# SCH_USB-Hub_2024-07-14.net
KiCad netlist of a schematic drawn in EasyEDA
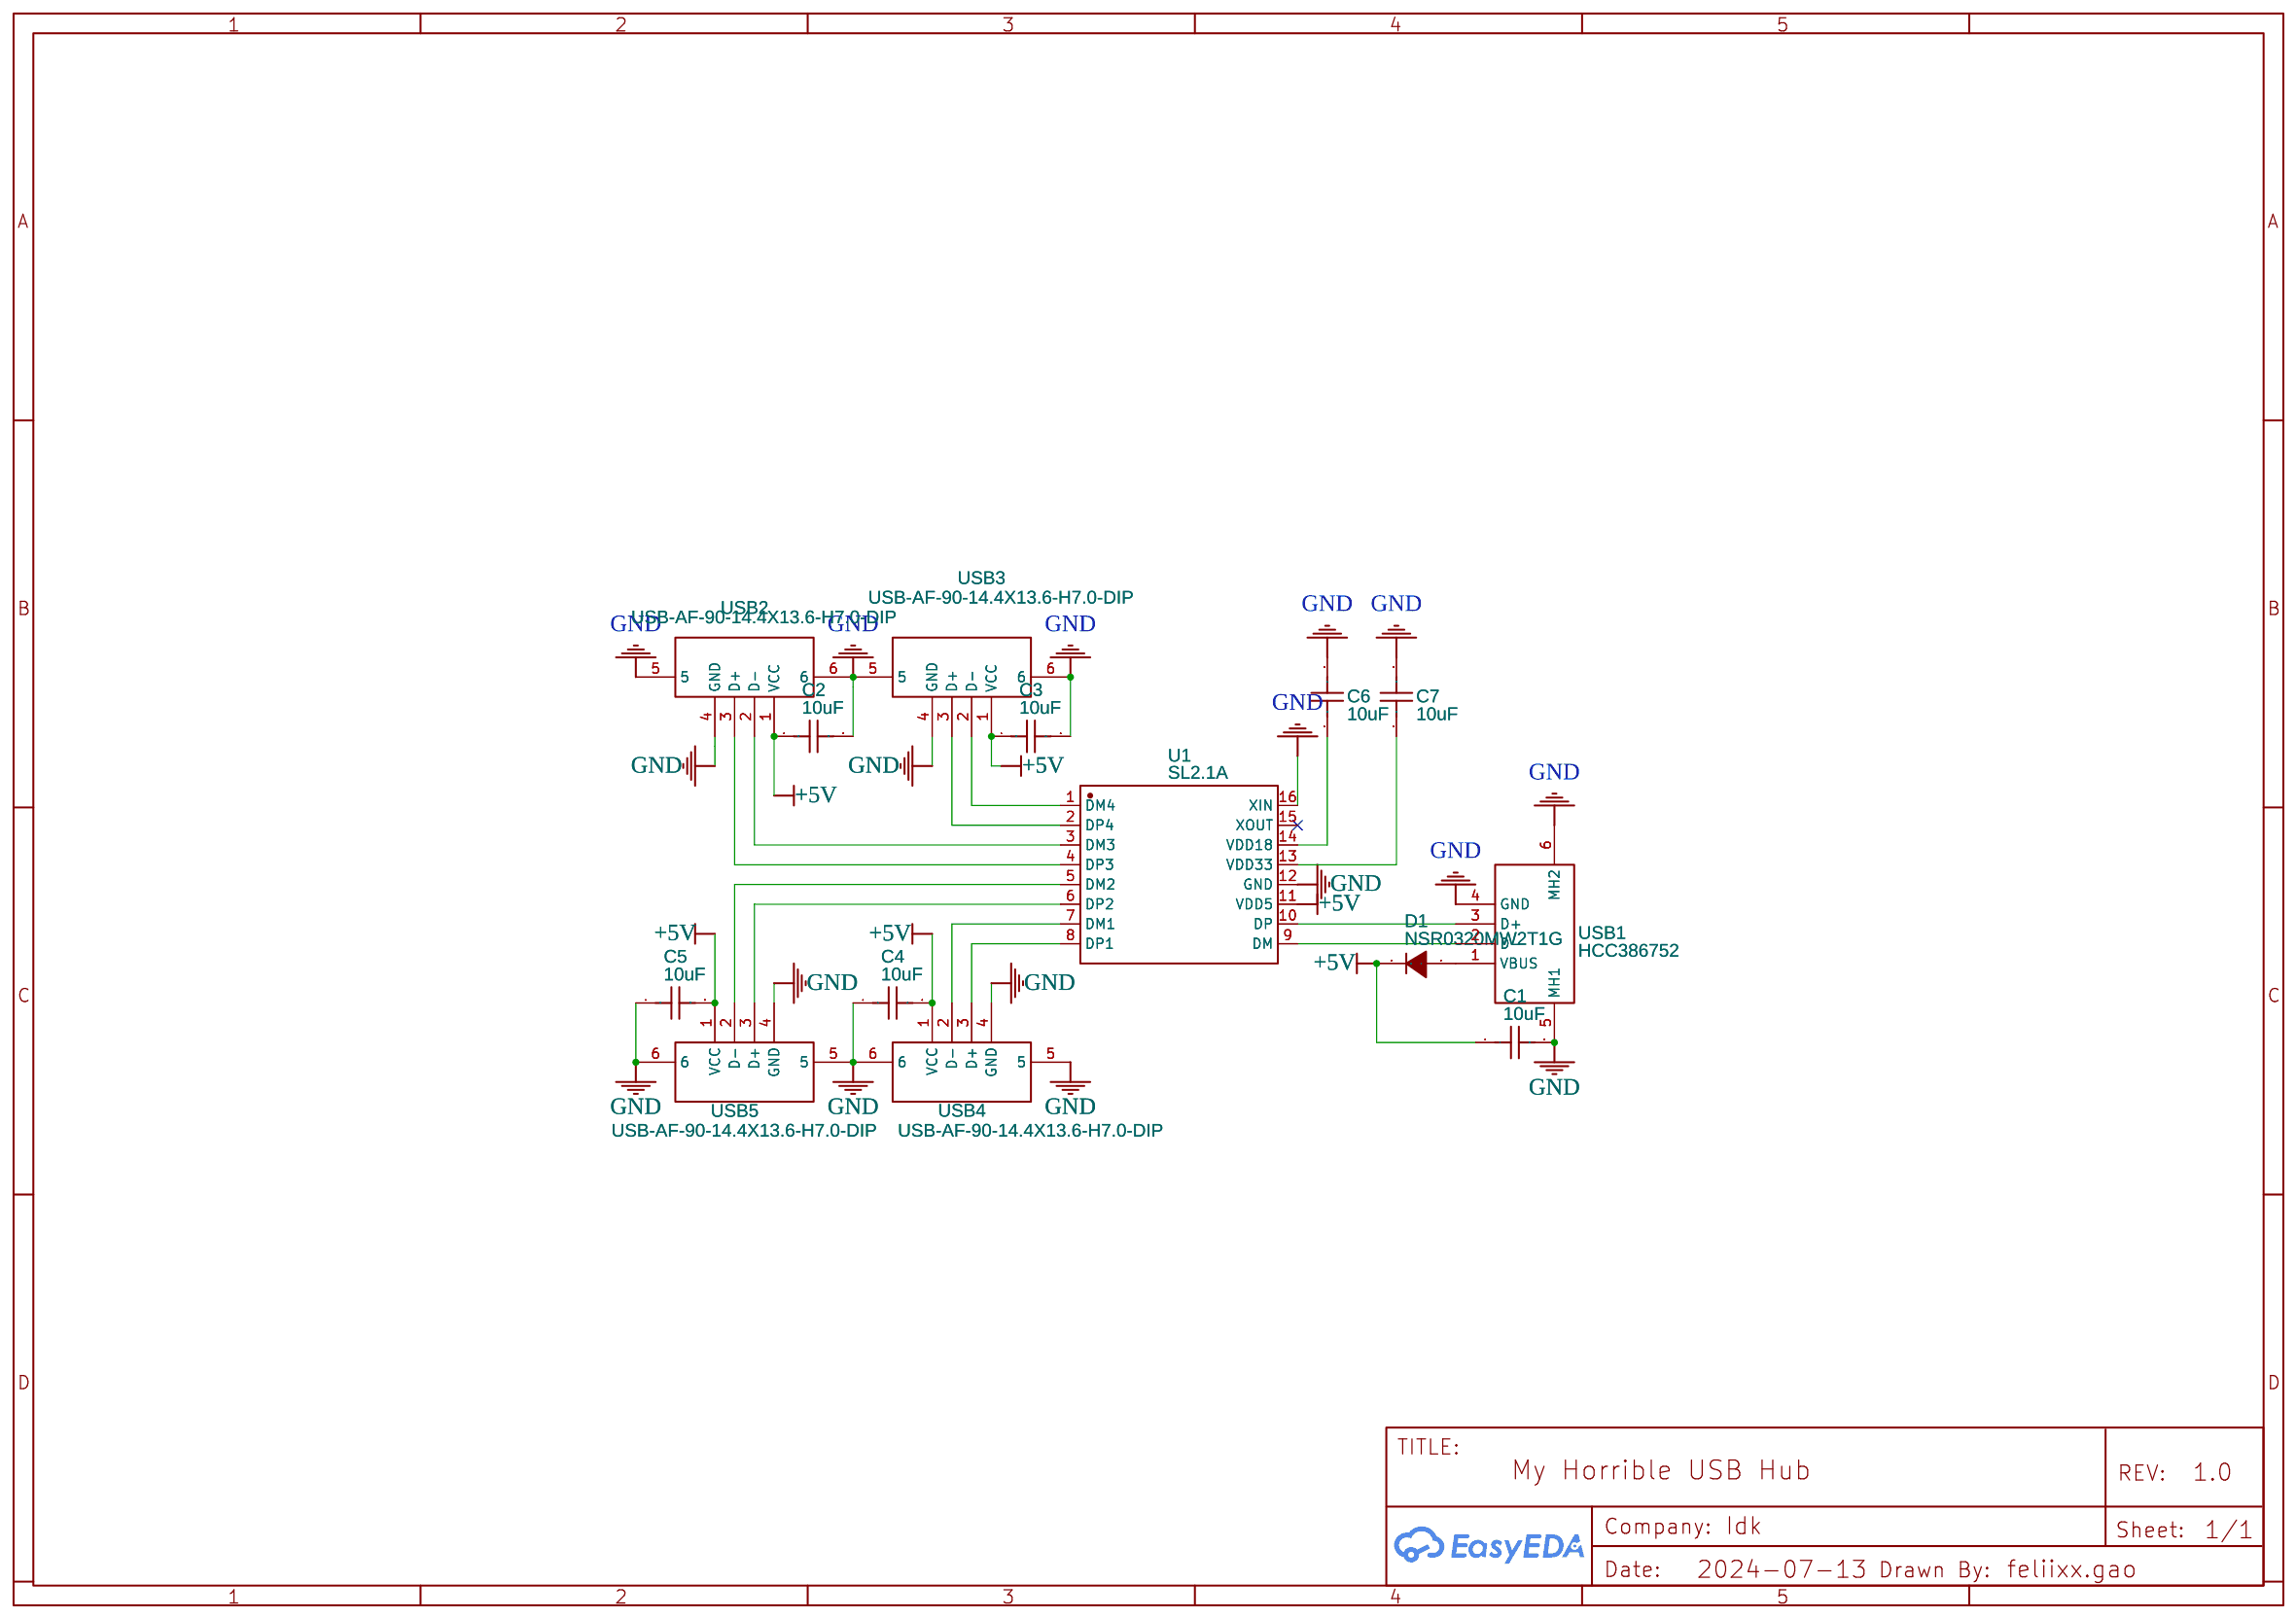
[diagram p0: schematic sheet]

(export (version "E")
  (design (tool "Eeschema 10.0.6"))
  (components
    (comp (ref "C1")
      (value "10uF")
      (fields
        (field (name "Manufacturer Part") "CL10A106KP8NNNC")
        (field (name "Manufacturer") "SAMSUNG(三星)")
      )
      (libsource (lib "") (part "CL10A106KP8NNNC"))
    )
    (comp (ref "C2")
      (value "10uF")
      (fields
        (field (name "Manufacturer Part") "CL10A106KP8NNNC")
        (field (name "Manufacturer") "SAMSUNG(三星)")
      )
      (libsource (lib "") (part "CL10A106KP8NNNC"))
    )
    (comp (ref "C3")
      (value "10uF")
      (fields
        (field (name "Manufacturer Part") "CL10A106KP8NNNC")
        (field (name "Manufacturer") "SAMSUNG(三星)")
      )
      (libsource (lib "") (part "CL10A106KP8NNNC"))
    )
    (comp (ref "C4")
      (value "10uF")
      (fields
        (field (name "Manufacturer Part") "CL10A106KP8NNNC")
        (field (name "Manufacturer") "SAMSUNG(三星)")
      )
      (libsource (lib "") (part "CL10A106KP8NNNC"))
    )
    (comp (ref "C5")
      (value "10uF")
      (fields
        (field (name "Manufacturer Part") "CL10A106KP8NNNC")
        (field (name "Manufacturer") "SAMSUNG(三星)")
      )
      (libsource (lib "") (part "CL10A106KP8NNNC"))
    )
    (comp (ref "C6")
      (value "10uF")
      (fields
        (field (name "Manufacturer Part") "CL10A106KP8NNNC")
        (field (name "Manufacturer") "SAMSUNG(三星)")
      )
      (libsource (lib "") (part "CL10A106KP8NNNC_1"))
    )
    (comp (ref "C7")
      (value "10uF")
      (fields
        (field (name "Manufacturer Part") "CL10A106KP8NNNC")
        (field (name "Manufacturer") "SAMSUNG(三星)")
      )
      (libsource (lib "") (part "CL10A106KP8NNNC_1"))
    )
    (comp (ref "D1")
      (value "NSR0320MW2T1G")
      (fields (field (name "Manufacturer") "onsemi(安森美)"))
      (libsource (lib "") (part "NSR0320MW2T1G"))
    )
    (comp (ref "U1")
      (value "SL2.1A")
      (fields (field (name "Manufacturer") "CoreChips(和芯润德)"))
      (libsource (lib "") (part "SL2.1A"))
    )
    (comp (ref "USB1")
      (value "HCC386752")
      (fields (field (name "Manufacturer Part") "U-USBAR04P-M003") (field (name "Manufacturer") "Ckmtw(灿科盟)"))
      (libsource (lib "") (part "HCC386752"))
    )
    (comp (ref "USB2")
      (value "USB-AF-90-14.4X13.6-H7.0-DIP")
      (fields (field (name "Manufacturer Part") "903-131A1011D10100") (field (name "Manufacturer") "精拓金"))
      (libsource (lib "") (part "USB-AF-90-14.4X13.6-H7.0-DIP"))
    )
    (comp (ref "USB3")
      (value "USB-AF-90-14.4X13.6-H7.0-DIP")
      (fields (field (name "Manufacturer Part") "903-131A1011D10100") (field (name "Manufacturer") "精拓金"))
      (libsource (lib "") (part "USB-AF-90-14.4X13.6-H7.0-DIP"))
    )
    (comp (ref "USB4")
      (value "USB-AF-90-14.4X13.6-H7.0-DIP")
      (fields (field (name "Manufacturer Part") "903-131A1011D10100") (field (name "Manufacturer") "精拓金"))
      (libsource (lib "") (part "USB-AF-90-14.4X13.6-H7.0-DIP_1"))
    )
    (comp (ref "USB5")
      (value "USB-AF-90-14.4X13.6-H7.0-DIP")
      (fields (field (name "Manufacturer Part") "903-131A1011D10100") (field (name "Manufacturer") "精拓金"))
      (libsource (lib "") (part "USB-AF-90-14.4X13.6-H7.0-DIP_1"))
    )
  )
  (nets
    (net (code "1") (name "+5V") (class "Default")
      (node (ref "C1") (pin "1") (pinfunction "1_1") (pintype "unspecified"))
      (node (ref "C2") (pin "1") (pinfunction "1_1") (pintype "unspecified"))
      (node (ref "C3") (pin "1") (pinfunction "1_1") (pintype "unspecified"))
      (node (ref "C4") (pin "2") (pinfunction "2_2") (pintype "unspecified"))
      (node (ref "C5") (pin "2") (pinfunction "2_2") (pintype "unspecified"))
      (node (ref "D1") (pin "1") (pinfunction "C_1") (pintype "unspecified"))
      (node (ref "U1") (pin "11") (pinfunction "VDD5_11") (pintype "unspecified"))
      (node (ref "USB2") (pin "1") (pinfunction "VCC_1") (pintype "unspecified"))
      (node (ref "USB3") (pin "1") (pinfunction "VCC_1") (pintype "unspecified"))
      (node (ref "USB4") (pin "1") (pinfunction "VCC_1") (pintype "unspecified"))
      (node (ref "USB5") (pin "1") (pinfunction "VCC_1") (pintype "unspecified"))
    )
    (net (code "2") (name "GND") (class "Default")
      (node (ref "C1") (pin "2") (pinfunction "2_2") (pintype "unspecified"))
      (node (ref "C2") (pin "2") (pinfunction "2_2") (pintype "unspecified"))
      (node (ref "C3") (pin "2") (pinfunction "2_2") (pintype "unspecified"))
      (node (ref "C4") (pin "1") (pinfunction "1_1") (pintype "unspecified"))
      (node (ref "C5") (pin "1") (pinfunction "1_1") (pintype "unspecified"))
      (node (ref "C6") (pin "2") (pinfunction "2_2") (pintype "unspecified"))
      (node (ref "C7") (pin "2") (pinfunction "2_2") (pintype "unspecified"))
      (node (ref "U1") (pin "12") (pinfunction "GND_12") (pintype "unspecified"))
      (node (ref "U1") (pin "16") (pinfunction "XIN_16") (pintype "unspecified"))
      (node (ref "USB1") (pin "4") (pinfunction "GND_4") (pintype "unspecified"))
      (node (ref "USB1") (pin "5") (pinfunction "MH1_5") (pintype "unspecified"))
      (node (ref "USB1") (pin "6") (pinfunction "MH2_6") (pintype "unspecified"))
      (node (ref "USB2") (pin "4") (pinfunction "GND_4") (pintype "unspecified"))
      (node (ref "USB2") (pin "5") (pinfunction "5_5") (pintype "unspecified"))
      (node (ref "USB2") (pin "6") (pinfunction "6_6") (pintype "unspecified"))
      (node (ref "USB3") (pin "4") (pinfunction "GND_4") (pintype "unspecified"))
      (node (ref "USB3") (pin "5") (pinfunction "5_5") (pintype "unspecified"))
      (node (ref "USB3") (pin "6") (pinfunction "6_6") (pintype "unspecified"))
      (node (ref "USB4") (pin "4") (pinfunction "GND_4") (pintype "unspecified"))
      (node (ref "USB4") (pin "5") (pinfunction "5_5") (pintype "unspecified"))
      (node (ref "USB4") (pin "6") (pinfunction "6_6") (pintype "unspecified"))
      (node (ref "USB5") (pin "4") (pinfunction "GND_4") (pintype "unspecified"))
      (node (ref "USB5") (pin "5") (pinfunction "5_5") (pintype "unspecified"))
      (node (ref "USB5") (pin "6") (pinfunction "6_6") (pintype "unspecified"))
    )
    (net (code "3") (name "Net-(D1-A)") (class "Default")
      (node (ref "D1") (pin "2") (pinfunction "A_2") (pintype "unspecified"))
      (node (ref "USB1") (pin "1") (pinfunction "VBUS_1") (pintype "unspecified"))
    )
    (net (code "4") (name "Net-(U1-DM)") (class "Default")
      (node (ref "U1") (pin "9") (pinfunction "DM_9") (pintype "unspecified"))
      (node (ref "USB1") (pin "2") (pinfunction "D-_2") (pintype "unspecified"))
    )
    (net (code "5") (name "Net-(U1-DM1)") (class "Default")
      (node (ref "U1") (pin "7") (pinfunction "DM1_7") (pintype "unspecified"))
      (node (ref "USB4") (pin "2") (pinfunction "D-_2") (pintype "unspecified"))
    )
    (net (code "6") (name "Net-(U1-DM2)") (class "Default")
      (node (ref "U1") (pin "5") (pinfunction "DM2_5") (pintype "unspecified"))
      (node (ref "USB5") (pin "2") (pinfunction "D-_2") (pintype "unspecified"))
    )
    (net (code "7") (name "Net-(U1-DM3)") (class "Default")
      (node (ref "U1") (pin "3") (pinfunction "DM3_3") (pintype "unspecified"))
      (node (ref "USB2") (pin "2") (pinfunction "D-_2") (pintype "unspecified"))
    )
    (net (code "8") (name "Net-(U1-DM4)") (class "Default")
      (node (ref "U1") (pin "1") (pinfunction "DM4_1") (pintype "unspecified"))
      (node (ref "USB3") (pin "2") (pinfunction "D-_2") (pintype "unspecified"))
    )
    (net (code "9") (name "Net-(U1-DP)") (class "Default")
      (node (ref "U1") (pin "10") (pinfunction "DP_10") (pintype "unspecified"))
      (node (ref "USB1") (pin "3") (pinfunction "D+_3") (pintype "unspecified"))
    )
    (net (code "10") (name "Net-(U1-DP1)") (class "Default")
      (node (ref "U1") (pin "8") (pinfunction "DP1_8") (pintype "unspecified"))
      (node (ref "USB4") (pin "3") (pinfunction "D+_3") (pintype "unspecified"))
    )
    (net (code "11") (name "Net-(U1-DP2)") (class "Default")
      (node (ref "U1") (pin "6") (pinfunction "DP2_6") (pintype "unspecified"))
      (node (ref "USB5") (pin "3") (pinfunction "D+_3") (pintype "unspecified"))
    )
    (net (code "12") (name "Net-(U1-DP3)") (class "Default")
      (node (ref "U1") (pin "4") (pinfunction "DP3_4") (pintype "unspecified"))
      (node (ref "USB2") (pin "3") (pinfunction "D+_3") (pintype "unspecified"))
    )
    (net (code "13") (name "Net-(U1-DP4)") (class "Default")
      (node (ref "U1") (pin "2") (pinfunction "DP4_2") (pintype "unspecified"))
      (node (ref "USB3") (pin "3") (pinfunction "D+_3") (pintype "unspecified"))
    )
    (net (code "14") (name "Net-(U1-VDD18)") (class "Default")
      (node (ref "C6") (pin "1") (pinfunction "1_1") (pintype "unspecified"))
      (node (ref "U1") (pin "14") (pinfunction "VDD18_14") (pintype "unspecified"))
    )
    (net (code "15") (name "Net-(U1-VDD33)") (class "Default")
      (node (ref "C7") (pin "1") (pinfunction "1_1") (pintype "unspecified"))
      (node (ref "U1") (pin "13") (pinfunction "VDD33_13") (pintype "unspecified"))
    )
    (net (code "16") (name "unconnected-(U1-XOUT-Pad15)") (class "Default")
      (node (ref "U1") (pin "15") (pinfunction "XOUT_15") (pintype "unspecified+no_connect"))
    )
  )
)
